# Microcontroller.net
KiCad netlist of a schematic drawn in Altium Designer
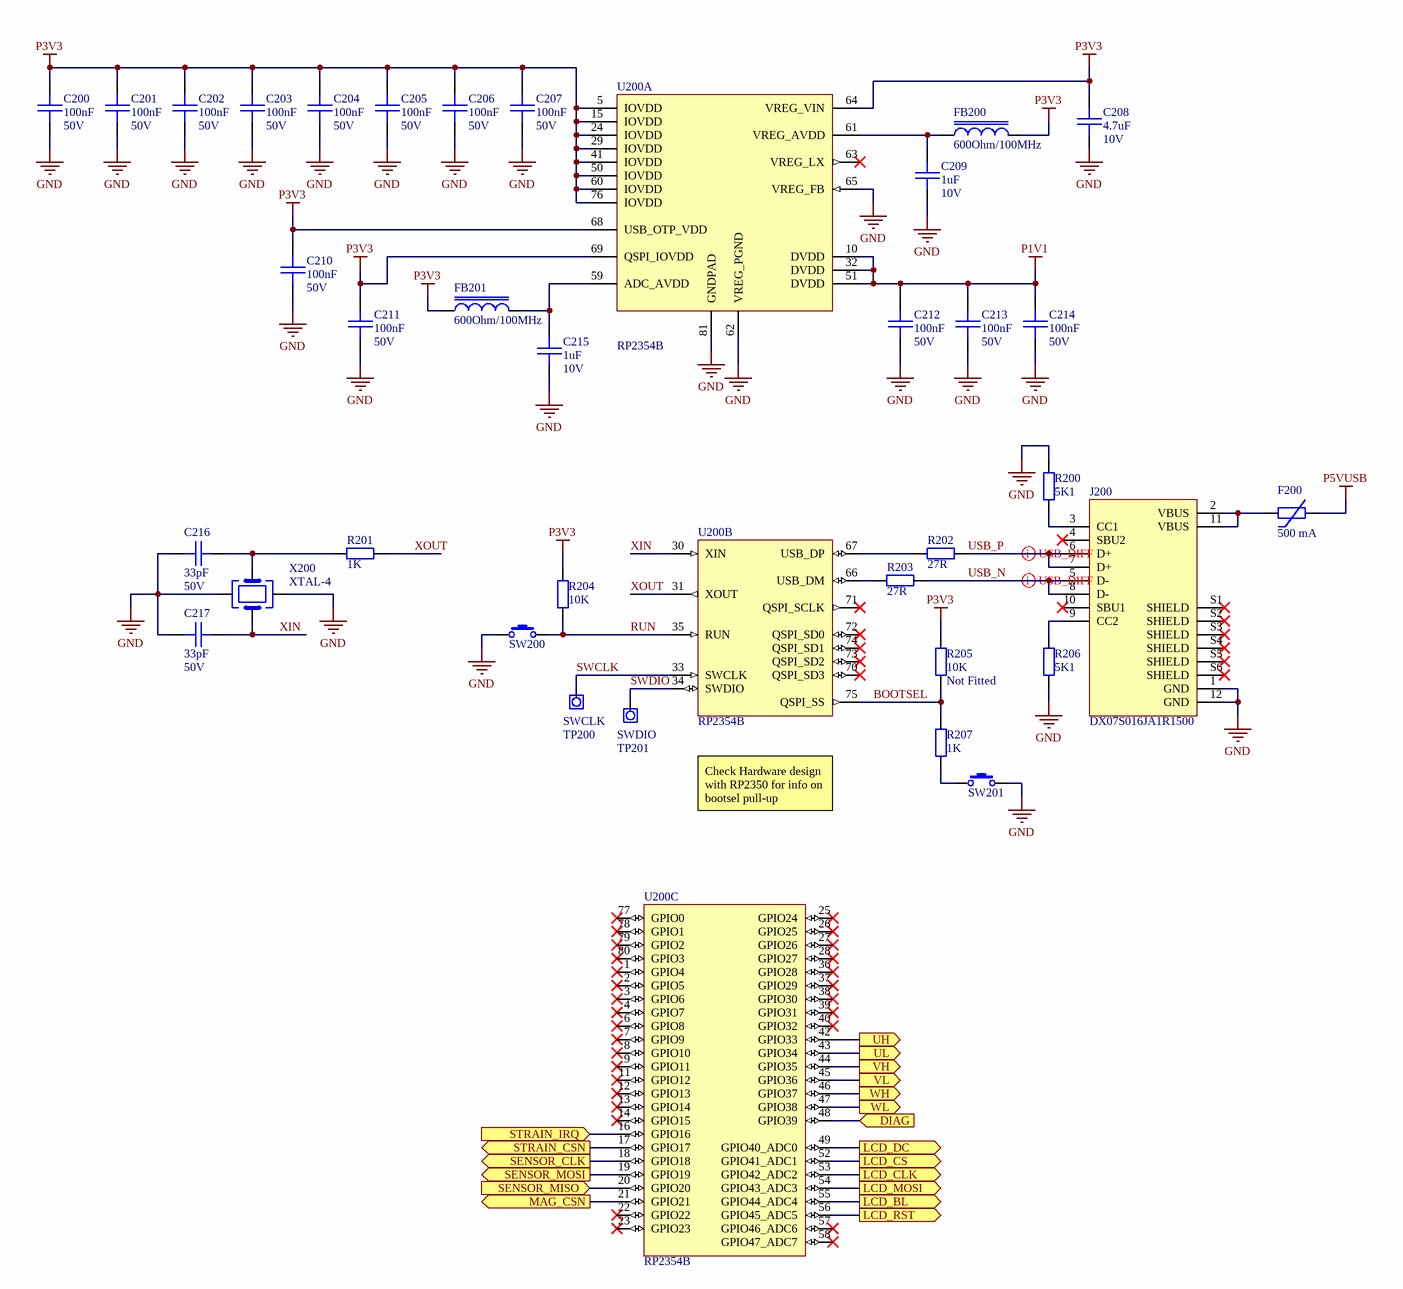
[diagram p0: Microcontroller.SchDoc]

(export (version "E")
  (design (tool "Eeschema 10.0.6"))
  (components
    (comp (ref "C200")
      (value "100nF")
      (footprint "C0402")
      (description "General purpose ceramic capacitor")
      (fields
        (field (name "VOLTAGE") "50V")
        (field (name "MANUFACTURER") "Murata Electronics")
        (field (name "MANUFACTURER PART NO") "GRT155R71H104KE01D")
      )
      (libsource (lib "Moonlight_Library") (part "CAP"))
    )
    (comp (ref "C201")
      (value "100nF")
      (footprint "C0402")
      (description "General purpose ceramic capacitor")
      (fields
        (field (name "VOLTAGE") "50V")
        (field (name "MANUFACTURER") "Murata Electronics")
        (field (name "MANUFACTURER PART NO") "GRT155R71H104KE01D")
      )
      (libsource (lib "Moonlight_Library") (part "CAP"))
    )
    (comp (ref "C202")
      (value "100nF")
      (footprint "C0402")
      (description "General purpose ceramic capacitor")
      (fields
        (field (name "VOLTAGE") "50V")
        (field (name "MANUFACTURER") "Murata Electronics")
        (field (name "MANUFACTURER PART NO") "GRT155R71H104KE01D")
      )
      (libsource (lib "Moonlight_Library") (part "CAP"))
    )
    (comp (ref "C203")
      (value "100nF")
      (footprint "C0402")
      (description "General purpose ceramic capacitor")
      (fields
        (field (name "VOLTAGE") "50V")
        (field (name "MANUFACTURER") "Murata Electronics")
        (field (name "MANUFACTURER PART NO") "GRT155R71H104KE01D")
      )
      (libsource (lib "Moonlight_Library") (part "CAP"))
    )
    (comp (ref "C204")
      (value "100nF")
      (footprint "C0402")
      (description "General purpose ceramic capacitor")
      (fields
        (field (name "VOLTAGE") "50V")
        (field (name "MANUFACTURER") "Murata Electronics")
        (field (name "MANUFACTURER PART NO") "GRT155R71H104KE01D")
      )
      (libsource (lib "Moonlight_Library") (part "CAP"))
    )
    (comp (ref "C205")
      (value "100nF")
      (footprint "C0402")
      (description "General purpose ceramic capacitor")
      (fields
        (field (name "VOLTAGE") "50V")
        (field (name "MANUFACTURER") "Murata Electronics")
        (field (name "MANUFACTURER PART NO") "GRT155R71H104KE01D")
      )
      (libsource (lib "Moonlight_Library") (part "CAP"))
    )
    (comp (ref "C206")
      (value "100nF")
      (footprint "C0402")
      (description "General purpose ceramic capacitor")
      (fields
        (field (name "VOLTAGE") "50V")
        (field (name "MANUFACTURER") "Murata Electronics")
        (field (name "MANUFACTURER PART NO") "GRT155R71H104KE01D")
      )
      (libsource (lib "Moonlight_Library") (part "CAP"))
    )
    (comp (ref "C207")
      (value "100nF")
      (footprint "C0402")
      (description "General purpose ceramic capacitor")
      (fields
        (field (name "VOLTAGE") "50V")
        (field (name "MANUFACTURER") "Murata Electronics")
        (field (name "MANUFACTURER PART NO") "GRT155R71H104KE01D")
      )
      (libsource (lib "Moonlight_Library") (part "CAP"))
    )
    (comp (ref "C208")
      (value "4.7uF")
      (footprint "C0402")
      (description "General purpose ceramic capacitor")
      (fields
        (field (name "VOLTAGE") "10V")
        (field (name "MANUFACTURER") "Murata Electronics")
        (field (name "MANUFACTURER PART NO") "GRT155R61A475ME13D")
      )
      (libsource (lib "Moonlight_Library") (part "CAP"))
    )
    (comp (ref "C209")
      (value "1uF")
      (footprint "C0402")
      (description "General purpose ceramic capacitor")
      (fields
        (field (name "VOLTAGE") "10V")
        (field (name "MANUFACTURER") "Murata Electronics")
        (field (name "MANUFACTURER PART NO") "GRT155R61A105KE01D")
      )
      (libsource (lib "Moonlight_Library") (part "CAP"))
    )
    (comp (ref "C210")
      (value "100nF")
      (footprint "C0402")
      (description "General purpose ceramic capacitor")
      (fields
        (field (name "VOLTAGE") "50V")
        (field (name "MANUFACTURER") "Murata Electronics")
        (field (name "MANUFACTURER PART NO") "GRT155R71H104KE01D")
      )
      (libsource (lib "Moonlight_Library") (part "CAP"))
    )
    (comp (ref "C211")
      (value "100nF")
      (footprint "C0402")
      (description "General purpose ceramic capacitor")
      (fields
        (field (name "VOLTAGE") "50V")
        (field (name "MANUFACTURER") "Murata Electronics")
        (field (name "MANUFACTURER PART NO") "GRT155R71H104KE01D")
      )
      (libsource (lib "Moonlight_Library") (part "CAP"))
    )
    (comp (ref "C212")
      (value "100nF")
      (footprint "C0402")
      (description "General purpose ceramic capacitor")
      (fields
        (field (name "VOLTAGE") "50V")
        (field (name "MANUFACTURER") "Murata Electronics")
        (field (name "MANUFACTURER PART NO") "GRT155R71H104KE01D")
      )
      (libsource (lib "Moonlight_Library") (part "CAP"))
    )
    (comp (ref "C213")
      (value "100nF")
      (footprint "C0402")
      (description "General purpose ceramic capacitor")
      (fields
        (field (name "VOLTAGE") "50V")
        (field (name "MANUFACTURER") "Murata Electronics")
        (field (name "MANUFACTURER PART NO") "GRT155R71H104KE01D")
      )
      (libsource (lib "Moonlight_Library") (part "CAP"))
    )
    (comp (ref "C214")
      (value "100nF")
      (footprint "C0402")
      (description "General purpose ceramic capacitor")
      (fields
        (field (name "VOLTAGE") "50V")
        (field (name "MANUFACTURER") "Murata Electronics")
        (field (name "MANUFACTURER PART NO") "GRT155R71H104KE01D")
      )
      (libsource (lib "Moonlight_Library") (part "CAP"))
    )
    (comp (ref "C215")
      (value "1uF")
      (footprint "C0402")
      (description "General purpose ceramic capacitor")
      (fields
        (field (name "VOLTAGE") "10V")
        (field (name "MANUFACTURER") "Murata Electronics")
        (field (name "MANUFACTURER PART NO") "GRT155R61A105KE01D")
      )
      (libsource (lib "Moonlight_Library") (part "CAP"))
    )
    (comp (ref "C216")
      (value "33pF")
      (footprint "C0603")
      (description "General purpose ceramic capacitor")
      (fields
        (field (name "VOLTAGE") "50V")
        (field (name "MANUFACTURER") "TDK Corporation")
        (field (name "MANUFACTURER PART NO") "CGA3E2C0G1H330J080AA")
      )
      (libsource (lib "Moonlight_Library") (part "CAP"))
    )
    (comp (ref "C217")
      (value "33pF")
      (footprint "C0603")
      (description "General purpose ceramic capacitor")
      (fields
        (field (name "VOLTAGE") "50V")
        (field (name "MANUFACTURER") "TDK Corporation")
        (field (name "MANUFACTURER PART NO") "CGA3E2C0G1H330J080AA")
      )
      (libsource (lib "Moonlight_Library") (part "CAP"))
    )
    (comp (ref "F200")
      (value "500 mA")
      (footprint "F0805")
      (description "PTC resettable SMD fuse")
      (fields
        (field (name "MANUFACTURER") "Bourns Inc")
        (field (name "MANUFACTURER PART NO") "MF-PSMF050X-2")
      )
      (libsource (lib "Moonlight_Library") (part "F_PTC"))
    )
    (comp (ref "FB200")
      (value "600Ohm/100MHz")
      (footprint "0603_IND")
      (description "Ferrite bead")
      (fields
        (field (name "MANUFACTURER") "Murata Electronics")
        (field (name "MANUFACTURER PART NO") "BLM18KG601SH1D")
      )
      (libsource (lib "Moonlight_Library") (part "FBEAD"))
    )
    (comp (ref "FB201")
      (value "600Ohm/100MHz")
      (footprint "0603_IND")
      (description "Ferrite bead")
      (fields
        (field (name "MANUFACTURER") "Murata Electronics")
        (field (name "MANUFACTURER PART NO") "BLM18KG601SH1D")
      )
      (libsource (lib "Moonlight_Library") (part "FBEAD"))
    )
    (comp (ref "J200")
      (value "DX07S016JA1R1500")
      (footprint "DX07S016JA1R1500")
      (description "USB 2.0 Type C connector")
      (fields (field (name "MANUFACTURER") "JAE Electronics"))
      (libsource (lib "Moonlight_Library") (part "DX07S016JA1R1500"))
    )
    (comp (ref "R200")
      (value "5K1")
      (footprint "R0402")
      (description "General purpose resistor")
      (fields (field (name "MANUFACTURER PART NO") "Generic resistor") (field (name "Comment") "RES"))
      (libsource (lib "Moonlight_Library") (part "RES"))
    )
    (comp (ref "R201")
      (value "1K")
      (footprint "R0603")
      (description "General purpose automotive thick film resistor")
      (fields
        (field (name "MANUFACTURER") "Vishay Dale")
        (field (name "MANUFACTURER PART NO") "CRCW06031K00JNEA")
      )
      (libsource (lib "") (part "RES_1"))
    )
    (comp (ref "R202")
      (value "27R")
      (footprint "R0402")
      (description "General purpose resistor")
      (fields (field (name "MANUFACTURER PART NO") "Generic resistor") (field (name "Comment") "RES"))
      (libsource (lib "") (part "RES_1"))
    )
    (comp (ref "R203")
      (value "27R")
      (footprint "R0402")
      (description "General purpose resistor")
      (fields (field (name "MANUFACTURER PART NO") "Generic resistor") (field (name "Comment") "RES"))
      (libsource (lib "") (part "RES_1"))
    )
    (comp (ref "R204")
      (value "10K")
      (footprint "R0402")
      (description "General purpose resistor")
      (fields (field (name "MANUFACTURER PART NO") "Generic resistor") (field (name "Comment") "RES"))
      (libsource (lib "Moonlight_Library") (part "RES"))
    )
    (comp (ref "R205")
      (value "10K")
      (footprint "R0402")
      (description "General purpose resistor")
      (fields
        (field (name "FITTED") "Not Fitted")
        (field (name "MANUFACTURER PART NO") "Generic resistor")
        (field (name "Comment") "RES")
      )
      (libsource (lib "Moonlight_Library") (part "RES"))
    )
    (comp (ref "R206")
      (value "5K1")
      (footprint "R0402")
      (description "General purpose resistor")
      (fields (field (name "MANUFACTURER PART NO") "Generic resistor") (field (name "Comment") "RES"))
      (libsource (lib "Moonlight_Library") (part "RES"))
    )
    (comp (ref "R207")
      (value "1K")
      (footprint "R0402")
      (description "General purpose resistor")
      (fields (field (name "MANUFACTURER PART NO") "Generic resistor") (field (name "Comment") "RES"))
      (libsource (lib "Moonlight_Library") (part "RES"))
    )
    (comp (ref "SW200")
      (value "Pushbutton")
      (footprint "434133025816")
      (description "SPST Tactile Switch 4.2x3.2 mm")
      (fields
        (field (name "MANUFACTURER") "Wurth Elektronik")
        (field (name "MANUFACTURER PART NO") "434133025816")
      )
      (libsource (lib "Moonlight_Library") (part "Pushbutton"))
    )
    (comp (ref "SW201")
      (value "Pushbutton")
      (footprint "434133025816")
      (description "SPST Tactile Switch 4.2x3.2 mm")
      (fields
        (field (name "MANUFACTURER") "Wurth Elektronik")
        (field (name "MANUFACTURER PART NO") "434133025816")
      )
      (libsource (lib "Moonlight_Library") (part "Pushbutton"))
    )
    (comp (ref "TP200")
      (value "SWCLK")
      (footprint "TP_SMD")
      (description "SMD Testpoint, pad style")
      (libsource (lib "Moonlight_Library") (part "Testpoint"))
    )
    (comp (ref "TP201")
      (value "SWDIO")
      (footprint "TP_SMD")
      (description "SMD Testpoint, pad style")
      (libsource (lib "Moonlight_Library") (part "Testpoint"))
    )
    (comp (ref "U200")
      (value "RP235xB")
      (footprint "RP235xB")
      (description "Dual Core 150 MHz ARM-M33 Microcontroller with 2 MB Flash")
      (fields (field (name "MANUFACTURER PART NO") "RP2354B") (field (name "MANUFACTURER") "Raspberry Pi"))
      (libsource (lib "Moonlight_Library") (part "RP235xB"))
    )
    (comp (ref "X200")
      (value "XTAL-4")
      (footprint "XTAL 3.2x2.5mm")
      (description "12 MHz 10ppm crystal oscillator")
      (fields
        (field (name "MANUFACTURER") "ECS Inc")
        (field (name "MANUFACTURER PART NO") "ECS-120-20-33-CKM-TR")
      )
      (libsource (lib "Moonlight_Library") (part "XTAL-4"))
    )
  )
  (nets
    (net (code "1") (name "/BOOTSEL") (class "Default")
      (node (ref "R205") (pin "1") (pintype "passive"))
      (node (ref "R207") (pin "2") (pintype "passive"))
      (node (ref "U200") (pin "75") (pinfunction "QSPI_SS_75") (pintype "output"))
    )
    (net (code "2") (name "/DIAG") (class "Default")
      (node (ref "U200") (pin "48") (pinfunction "GPIO39_48") (pintype "bidirectional"))
    )
    (net (code "3") (name "/LCD_BL") (class "Default")
      (node (ref "U200") (pin "55") (pinfunction "GPIO44_ADC4_55") (pintype "bidirectional"))
    )
    (net (code "4") (name "/LCD_CLK") (class "Default")
      (node (ref "U200") (pin "53") (pinfunction "GPIO42_ADC2_53") (pintype "bidirectional"))
    )
    (net (code "5") (name "/LCD_CS") (class "Default")
      (node (ref "U200") (pin "52") (pinfunction "GPIO41_ADC1_52") (pintype "bidirectional"))
    )
    (net (code "6") (name "/LCD_DC") (class "Default")
      (node (ref "U200") (pin "49") (pinfunction "GPIO40_ADC0_49") (pintype "bidirectional"))
    )
    (net (code "7") (name "/LCD_MOSI") (class "Default")
      (node (ref "U200") (pin "54") (pinfunction "GPIO43_ADC3_54") (pintype "bidirectional"))
    )
    (net (code "8") (name "/LCD_RST") (class "Default")
      (node (ref "U200") (pin "56") (pinfunction "GPIO45_ADC5_56") (pintype "bidirectional"))
    )
    (net (code "9") (name "/MAG_CSN") (class "Default")
      (node (ref "U200") (pin "21") (pinfunction "GPIO21_21") (pintype "bidirectional"))
    )
    (net (code "10") (name "/RUN") (class "Default")
      (node (ref "R204") (pin "1") (pintype "passive"))
      (node (ref "SW200") (pin "2") (pintype "passive"))
      (node (ref "U200") (pin "35") (pinfunction "RUN_35") (pintype "input"))
    )
    (net (code "11") (name "/SENSOR_CLK") (class "Default")
      (node (ref "U200") (pin "18") (pinfunction "GPIO18_18") (pintype "bidirectional"))
    )
    (net (code "12") (name "/SENSOR_MISO") (class "Default")
      (node (ref "U200") (pin "20") (pinfunction "GPIO20_20") (pintype "bidirectional"))
    )
    (net (code "13") (name "/SENSOR_MOSI") (class "Default")
      (node (ref "U200") (pin "19") (pinfunction "GPIO19_19") (pintype "bidirectional"))
    )
    (net (code "14") (name "/STRAIN_CSN") (class "Default")
      (node (ref "U200") (pin "17") (pinfunction "GPIO17_17") (pintype "bidirectional"))
    )
    (net (code "15") (name "/STRAIN_IRQ") (class "Default")
      (node (ref "U200") (pin "16") (pinfunction "GPIO16_16") (pintype "bidirectional"))
    )
    (net (code "16") (name "/SWCLK") (class "Default")
      (node (ref "TP200") (pin "1") (pinfunction "1_1") (pintype "passive"))
      (node (ref "U200") (pin "33") (pinfunction "SWCLK_33") (pintype "input"))
    )
    (net (code "17") (name "/SWDIO") (class "Default")
      (node (ref "TP201") (pin "1") (pinfunction "1_1") (pintype "passive"))
      (node (ref "U200") (pin "34") (pinfunction "SWDIO_34") (pintype "bidirectional"))
    )
    (net (code "18") (name "/UH") (class "Default")
      (node (ref "U200") (pin "42") (pinfunction "GPIO33_42") (pintype "bidirectional"))
    )
    (net (code "19") (name "/UL") (class "Default")
      (node (ref "U200") (pin "43") (pinfunction "GPIO34_43") (pintype "bidirectional"))
    )
    (net (code "20") (name "/USB_N") (class "Default")
      (node (ref "J200") (pin "5") (pinfunction "D-_5") (pintype "passive"))
      (node (ref "J200") (pin "8") (pinfunction "D-_8") (pintype "passive"))
      (node (ref "R203") (pin "2") (pintype "passive"))
    )
    (net (code "21") (name "/USB_P") (class "Default")
      (node (ref "J200") (pin "6") (pinfunction "D+_6") (pintype "passive"))
      (node (ref "J200") (pin "7") (pinfunction "D+_7") (pintype "passive"))
      (node (ref "R202") (pin "2") (pintype "passive"))
    )
    (net (code "22") (name "/VH") (class "Default")
      (node (ref "U200") (pin "44") (pinfunction "GPIO35_44") (pintype "bidirectional"))
    )
    (net (code "23") (name "/VL") (class "Default")
      (node (ref "U200") (pin "45") (pinfunction "GPIO36_45") (pintype "bidirectional"))
    )
    (net (code "24") (name "/WH") (class "Default")
      (node (ref "U200") (pin "46") (pinfunction "GPIO37_46") (pintype "bidirectional"))
    )
    (net (code "25") (name "/WL") (class "Default")
      (node (ref "U200") (pin "47") (pinfunction "GPIO38_47") (pintype "bidirectional"))
    )
    (net (code "26") (name "/XIN") (class "Default")
      (node (ref "C217") (pin "2") (pinfunction "2_2") (pintype "passive"))
      (node (ref "U200") (pin "30") (pinfunction "XIN_30") (pintype "input"))
      (node (ref "X200") (pin "1") (pinfunction "1_1") (pintype "passive"))
    )
    (net (code "27") (name "/XOUT") (class "Default")
      (node (ref "R201") (pin "2") (pintype "passive"))
      (node (ref "U200") (pin "31") (pinfunction "XOUT_31") (pintype "output"))
    )
    (net (code "28") (name "GND") (class "Default")
      (node (ref "C200") (pin "2") (pinfunction "2_2") (pintype "passive"))
      (node (ref "C201") (pin "2") (pinfunction "2_2") (pintype "passive"))
      (node (ref "C202") (pin "2") (pinfunction "2_2") (pintype "passive"))
      (node (ref "C203") (pin "2") (pinfunction "2_2") (pintype "passive"))
      (node (ref "C204") (pin "2") (pinfunction "2_2") (pintype "passive"))
      (node (ref "C205") (pin "2") (pinfunction "2_2") (pintype "passive"))
      (node (ref "C206") (pin "2") (pinfunction "2_2") (pintype "passive"))
      (node (ref "C207") (pin "2") (pinfunction "2_2") (pintype "passive"))
      (node (ref "C208") (pin "2") (pinfunction "2_2") (pintype "passive"))
      (node (ref "C209") (pin "2") (pinfunction "2_2") (pintype "passive"))
      (node (ref "C210") (pin "2") (pinfunction "2_2") (pintype "passive"))
      (node (ref "C211") (pin "2") (pinfunction "2_2") (pintype "passive"))
      (node (ref "C212") (pin "2") (pinfunction "2_2") (pintype "passive"))
      (node (ref "C213") (pin "2") (pinfunction "2_2") (pintype "passive"))
      (node (ref "C214") (pin "2") (pinfunction "2_2") (pintype "passive"))
      (node (ref "C215") (pin "2") (pinfunction "2_2") (pintype "passive"))
      (node (ref "C216") (pin "1") (pinfunction "1_1") (pintype "passive"))
      (node (ref "C217") (pin "1") (pinfunction "1_1") (pintype "passive"))
      (node (ref "J200") (pin "1") (pinfunction "GND_1") (pintype "power_in"))
      (node (ref "J200") (pin "12") (pinfunction "GND_12") (pintype "power_in"))
      (node (ref "R200") (pin "2") (pintype "passive"))
      (node (ref "R206") (pin "1") (pintype "passive"))
      (node (ref "SW200") (pin "1") (pintype "passive"))
      (node (ref "SW201") (pin "2") (pintype "passive"))
      (node (ref "U200") (pin "62") (pinfunction "VREG_PGND_62") (pintype "power_in"))
      (node (ref "U200") (pin "65") (pinfunction "VREG_FB_65") (pintype "input"))
      (node (ref "U200") (pin "81") (pinfunction "GNDPAD_81") (pintype "power_in"))
      (node (ref "X200") (pin "2") (pinfunction "2_2") (pintype "passive"))
      (node (ref "X200") (pin "4") (pinfunction "4_4") (pintype "passive"))
    )
    (net (code "29") (name "Net-(C216-Pad2)") (class "Default")
      (node (ref "C216") (pin "2") (pinfunction "2_2") (pintype "passive"))
      (node (ref "R201") (pin "1") (pintype "passive"))
      (node (ref "X200") (pin "3") (pinfunction "3_3") (pintype "passive"))
    )
    (net (code "30") (name "Net-(F200-Pad1)") (class "Default")
      (node (ref "F200") (pin "1") (pintype "passive"))
      (node (ref "J200") (pin "11") (pinfunction "VBUS_11") (pintype "power_in"))
      (node (ref "J200") (pin "2") (pinfunction "VBUS_2") (pintype "power_in"))
    )
    (net (code "31") (name "Net-(J200-CC1)") (class "Default")
      (node (ref "J200") (pin "3") (pinfunction "CC1_3") (pintype "passive"))
      (node (ref "R200") (pin "1") (pintype "passive"))
    )
    (net (code "32") (name "Net-(J200-CC2)") (class "Default")
      (node (ref "J200") (pin "9") (pinfunction "CC2_9") (pintype "passive"))
      (node (ref "R206") (pin "2") (pintype "passive"))
    )
    (net (code "33") (name "Net-(R207-Pad1)") (class "Default")
      (node (ref "R207") (pin "1") (pintype "passive"))
      (node (ref "SW201") (pin "1") (pintype "passive"))
    )
    (net (code "34") (name "Net-(U200A-ADC_AVDD)") (class "Default")
      (node (ref "C215") (pin "1") (pinfunction "1_1") (pintype "passive"))
      (node (ref "FB201") (pin "2") (pinfunction "2_2") (pintype "passive"))
      (node (ref "U200") (pin "59") (pinfunction "ADC_AVDD_59") (pintype "power_in"))
    )
    (net (code "35") (name "Net-(U200A-VREG_AVDD)") (class "Default")
      (node (ref "C209") (pin "1") (pinfunction "1_1") (pintype "passive"))
      (node (ref "FB200") (pin "1") (pinfunction "1_1") (pintype "passive"))
      (node (ref "U200") (pin "61") (pinfunction "VREG_AVDD_61") (pintype "power_in"))
    )
    (net (code "36") (name "Net-(U200B-USB_DM)") (class "Default")
      (node (ref "R203") (pin "1") (pintype "passive"))
      (node (ref "U200") (pin "66") (pinfunction "USB_DM_66") (pintype "bidirectional"))
    )
    (net (code "37") (name "Net-(U200B-USB_DP)") (class "Default")
      (node (ref "R202") (pin "1") (pintype "passive"))
      (node (ref "U200") (pin "67") (pinfunction "USB_DP_67") (pintype "bidirectional"))
    )
    (net (code "38") (name "P1V1") (class "Default")
      (node (ref "C212") (pin "1") (pinfunction "1_1") (pintype "passive"))
      (node (ref "C213") (pin "1") (pinfunction "1_1") (pintype "passive"))
      (node (ref "C214") (pin "1") (pinfunction "1_1") (pintype "passive"))
      (node (ref "U200") (pin "10") (pinfunction "DVDD_10") (pintype "power_in"))
      (node (ref "U200") (pin "32") (pinfunction "DVDD_32") (pintype "power_in"))
      (node (ref "U200") (pin "51") (pinfunction "DVDD_51") (pintype "power_in"))
    )
    (net (code "39") (name "P3V3") (class "Default")
      (node (ref "C200") (pin "1") (pinfunction "1_1") (pintype "passive"))
      (node (ref "C201") (pin "1") (pinfunction "1_1") (pintype "passive"))
      (node (ref "C202") (pin "1") (pinfunction "1_1") (pintype "passive"))
      (node (ref "C203") (pin "1") (pinfunction "1_1") (pintype "passive"))
      (node (ref "C204") (pin "1") (pinfunction "1_1") (pintype "passive"))
      (node (ref "C205") (pin "1") (pinfunction "1_1") (pintype "passive"))
      (node (ref "C206") (pin "1") (pinfunction "1_1") (pintype "passive"))
      (node (ref "C207") (pin "1") (pinfunction "1_1") (pintype "passive"))
      (node (ref "C208") (pin "1") (pinfunction "1_1") (pintype "passive"))
      (node (ref "C210") (pin "1") (pinfunction "1_1") (pintype "passive"))
      (node (ref "C211") (pin "1") (pinfunction "1_1") (pintype "passive"))
      (node (ref "FB200") (pin "2") (pinfunction "2_2") (pintype "passive"))
      (node (ref "FB201") (pin "1") (pinfunction "1_1") (pintype "passive"))
      (node (ref "R204") (pin "2") (pintype "passive"))
      (node (ref "R205") (pin "2") (pintype "passive"))
      (node (ref "U200") (pin "15") (pinfunction "IOVDD_15") (pintype "power_in"))
      (node (ref "U200") (pin "24") (pinfunction "IOVDD_24") (pintype "power_in"))
      (node (ref "U200") (pin "29") (pinfunction "IOVDD_29") (pintype "power_in"))
      (node (ref "U200") (pin "41") (pinfunction "IOVDD_41") (pintype "power_in"))
      (node (ref "U200") (pin "5") (pinfunction "IOVDD_5") (pintype "power_in"))
      (node (ref "U200") (pin "50") (pinfunction "IOVDD_50") (pintype "power_in"))
      (node (ref "U200") (pin "60") (pinfunction "IOVDD_60") (pintype "power_in"))
      (node (ref "U200") (pin "64") (pinfunction "VREG_VIN_64") (pintype "power_in"))
      (node (ref "U200") (pin "68") (pinfunction "USB_OTP_VDD_68") (pintype "power_in"))
      (node (ref "U200") (pin "69") (pinfunction "QSPI_IOVDD_69") (pintype "power_in"))
      (node (ref "U200") (pin "76") (pinfunction "IOVDD_76") (pintype "power_in"))
    )
    (net (code "40") (name "P5VUSB") (class "Default")
      (node (ref "F200") (pin "2") (pinfunction "2_2") (pintype "passive"))
    )
    (net (code "41") (name "unconnected-(J200-SBU1-Pad10)") (class "Default")
      (node (ref "J200") (pin "10") (pinfunction "SBU1_10") (pintype "passive+no_connect"))
    )
    (net (code "42") (name "unconnected-(J200-SBU2-Pad4)") (class "Default")
      (node (ref "J200") (pin "4") (pinfunction "SBU2_4") (pintype "passive+no_connect"))
    )
    (net (code "43") (name "unconnected-(J200-SHIELD-PadS1)") (class "Default")
      (node (ref "J200") (pin "S1") (pinfunction "SHIELD_S1") (pintype "passive+no_connect"))
    )
    (net (code "44") (name "unconnected-(J200-SHIELD-PadS2)") (class "Default")
      (node (ref "J200") (pin "S2") (pinfunction "SHIELD_S2") (pintype "passive+no_connect"))
    )
    (net (code "45") (name "unconnected-(J200-SHIELD-PadS3)") (class "Default")
      (node (ref "J200") (pin "S3") (pinfunction "SHIELD_S3") (pintype "passive+no_connect"))
    )
    (net (code "46") (name "unconnected-(J200-SHIELD-PadS4)") (class "Default")
      (node (ref "J200") (pin "S4") (pinfunction "SHIELD_S4") (pintype "passive+no_connect"))
    )
    (net (code "47") (name "unconnected-(J200-SHIELD-PadS5)") (class "Default")
      (node (ref "J200") (pin "S5") (pinfunction "SHIELD_S5") (pintype "passive+no_connect"))
    )
    (net (code "48") (name "unconnected-(J200-SHIELD-PadS6)") (class "Default")
      (node (ref "J200") (pin "S6") (pinfunction "SHIELD_S6") (pintype "passive+no_connect"))
    )
    (net (code "49") (name "unconnected-(U200A-VREG_LX-Pad63)") (class "Default")
      (node (ref "U200") (pin "63") (pinfunction "VREG_LX_63") (pintype "output+no_connect"))
    )
    (net (code "50") (name "unconnected-(U200B-QSPI_SCLK-Pad71)") (class "Default")
      (node (ref "U200") (pin "71") (pinfunction "QSPI_SCLK_71") (pintype "output+no_connect"))
    )
    (net (code "51") (name "unconnected-(U200B-QSPI_SD0-Pad72)") (class "Default")
      (node (ref "U200") (pin "72") (pinfunction "QSPI_SD0_72") (pintype "bidirectional+no_connect"))
    )
    (net (code "52") (name "unconnected-(U200B-QSPI_SD1-Pad74)") (class "Default")
      (node (ref "U200") (pin "74") (pinfunction "QSPI_SD1_74") (pintype "bidirectional+no_connect"))
    )
    (net (code "53") (name "unconnected-(U200B-QSPI_SD2-Pad73)") (class "Default")
      (node (ref "U200") (pin "73") (pinfunction "QSPI_SD2_73") (pintype "bidirectional+no_connect"))
    )
    (net (code "54") (name "unconnected-(U200B-QSPI_SD3-Pad70)") (class "Default")
      (node (ref "U200") (pin "70") (pinfunction "QSPI_SD3_70") (pintype "bidirectional+no_connect"))
    )
    (net (code "55") (name "unconnected-(U200C-GPIO0-Pad77)") (class "Default")
      (node (ref "U200") (pin "77") (pinfunction "GPIO0_77") (pintype "bidirectional+no_connect"))
    )
    (net (code "56") (name "unconnected-(U200C-GPIO1-Pad78)") (class "Default")
      (node (ref "U200") (pin "78") (pinfunction "GPIO1_78") (pintype "bidirectional+no_connect"))
    )
    (net (code "57") (name "unconnected-(U200C-GPIO2-Pad79)") (class "Default")
      (node (ref "U200") (pin "79") (pinfunction "GPIO2_79") (pintype "bidirectional+no_connect"))
    )
    (net (code "58") (name "unconnected-(U200C-GPIO3-Pad80)") (class "Default")
      (node (ref "U200") (pin "80") (pinfunction "GPIO3_80") (pintype "bidirectional+no_connect"))
    )
    (net (code "59") (name "unconnected-(U200C-GPIO4-Pad1)") (class "Default")
      (node (ref "U200") (pin "1") (pinfunction "GPIO4_1") (pintype "bidirectional+no_connect"))
    )
    (net (code "60") (name "unconnected-(U200C-GPIO5-Pad2)") (class "Default")
      (node (ref "U200") (pin "2") (pinfunction "GPIO5_2") (pintype "bidirectional+no_connect"))
    )
    (net (code "61") (name "unconnected-(U200C-GPIO6-Pad3)") (class "Default")
      (node (ref "U200") (pin "3") (pinfunction "GPIO6_3") (pintype "bidirectional+no_connect"))
    )
    (net (code "62") (name "unconnected-(U200C-GPIO7-Pad4)") (class "Default")
      (node (ref "U200") (pin "4") (pinfunction "GPIO7_4") (pintype "bidirectional+no_connect"))
    )
    (net (code "63") (name "unconnected-(U200C-GPIO8-Pad6)") (class "Default")
      (node (ref "U200") (pin "6") (pinfunction "GPIO8_6") (pintype "bidirectional+no_connect"))
    )
    (net (code "64") (name "unconnected-(U200C-GPIO9-Pad7)") (class "Default")
      (node (ref "U200") (pin "7") (pinfunction "GPIO9_7") (pintype "bidirectional+no_connect"))
    )
    (net (code "65") (name "unconnected-(U200C-GPIO10-Pad8)") (class "Default")
      (node (ref "U200") (pin "8") (pinfunction "GPIO10_8") (pintype "bidirectional+no_connect"))
    )
    (net (code "66") (name "unconnected-(U200C-GPIO11-Pad9)") (class "Default")
      (node (ref "U200") (pin "9") (pinfunction "GPIO11_9") (pintype "bidirectional+no_connect"))
    )
    (net (code "67") (name "unconnected-(U200C-GPIO12-Pad11)") (class "Default")
      (node (ref "U200") (pin "11") (pinfunction "GPIO12_11") (pintype "bidirectional+no_connect"))
    )
    (net (code "68") (name "unconnected-(U200C-GPIO13-Pad12)") (class "Default")
      (node (ref "U200") (pin "12") (pinfunction "GPIO13_12") (pintype "bidirectional+no_connect"))
    )
    (net (code "69") (name "unconnected-(U200C-GPIO14-Pad13)") (class "Default")
      (node (ref "U200") (pin "13") (pinfunction "GPIO14_13") (pintype "bidirectional+no_connect"))
    )
    (net (code "70") (name "unconnected-(U200C-GPIO15-Pad14)") (class "Default")
      (node (ref "U200") (pin "14") (pinfunction "GPIO15_14") (pintype "bidirectional+no_connect"))
    )
    (net (code "71") (name "unconnected-(U200C-GPIO22-Pad22)") (class "Default")
      (node (ref "U200") (pin "22") (pinfunction "GPIO22_22") (pintype "bidirectional+no_connect"))
    )
    (net (code "72") (name "unconnected-(U200C-GPIO23-Pad23)") (class "Default")
      (node (ref "U200") (pin "23") (pinfunction "GPIO23_23") (pintype "bidirectional+no_connect"))
    )
    (net (code "73") (name "unconnected-(U200C-GPIO24-Pad25)") (class "Default")
      (node (ref "U200") (pin "25") (pinfunction "GPIO24_25") (pintype "bidirectional+no_connect"))
    )
    (net (code "74") (name "unconnected-(U200C-GPIO25-Pad26)") (class "Default")
      (node (ref "U200") (pin "26") (pinfunction "GPIO25_26") (pintype "bidirectional+no_connect"))
    )
    (net (code "75") (name "unconnected-(U200C-GPIO26-Pad27)") (class "Default")
      (node (ref "U200") (pin "27") (pinfunction "GPIO26_27") (pintype "bidirectional+no_connect"))
    )
    (net (code "76") (name "unconnected-(U200C-GPIO27-Pad28)") (class "Default")
      (node (ref "U200") (pin "28") (pinfunction "GPIO27_28") (pintype "bidirectional+no_connect"))
    )
    (net (code "77") (name "unconnected-(U200C-GPIO28-Pad36)") (class "Default")
      (node (ref "U200") (pin "36") (pinfunction "GPIO28_36") (pintype "bidirectional+no_connect"))
    )
    (net (code "78") (name "unconnected-(U200C-GPIO29-Pad37)") (class "Default")
      (node (ref "U200") (pin "37") (pinfunction "GPIO29_37") (pintype "bidirectional+no_connect"))
    )
    (net (code "79") (name "unconnected-(U200C-GPIO30-Pad38)") (class "Default")
      (node (ref "U200") (pin "38") (pinfunction "GPIO30_38") (pintype "bidirectional+no_connect"))
    )
    (net (code "80") (name "unconnected-(U200C-GPIO31-Pad39)") (class "Default")
      (node (ref "U200") (pin "39") (pinfunction "GPIO31_39") (pintype "bidirectional+no_connect"))
    )
    (net (code "81") (name "unconnected-(U200C-GPIO32-Pad40)") (class "Default")
      (node (ref "U200") (pin "40") (pinfunction "GPIO32_40") (pintype "bidirectional+no_connect"))
    )
    (net (code "82") (name "unconnected-(U200C-GPIO46_ADC6-Pad57)") (class "Default")
      (node (ref "U200") (pin "57") (pinfunction "GPIO46_ADC6_57") (pintype "bidirectional+no_connect"))
    )
    (net (code "83") (name "unconnected-(U200C-GPIO47_ADC7-Pad58)") (class "Default")
      (node (ref "U200") (pin "58") (pinfunction "GPIO47_ADC7_58") (pintype "bidirectional+no_connect"))
    )
  )
)
